# TOP.net
KiCad netlist of a schematic drawn in Altium Designer
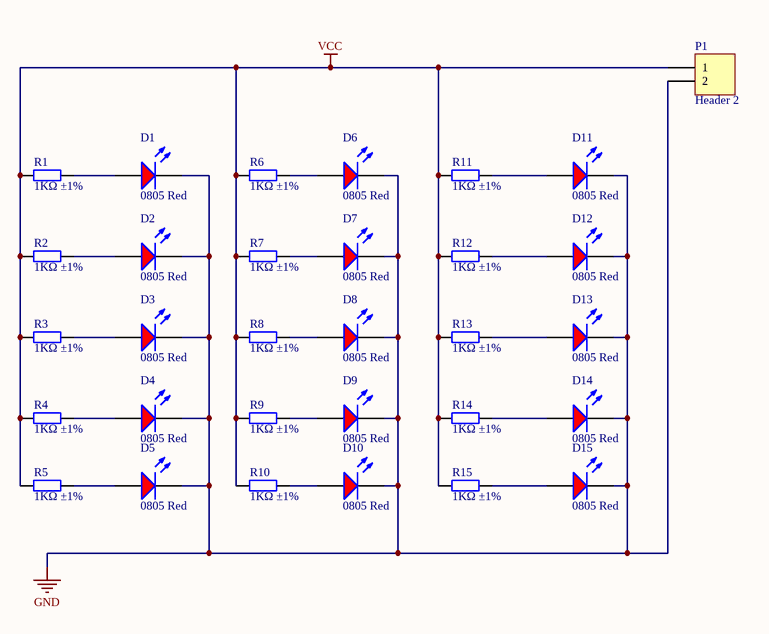
[diagram p0: TOP.SchDoc]

(export (version "E")
  (design (tool "Eeschema 10.0.6"))
  (components
    (comp (ref "D1")
      (value "0805 Red")
      (footprint "0805_LED_S1")
      (description "LED")
      (fields
        (field (name "PARTNUMBER") "FC-2012HRK-620D")
        (field (name "MANUFACTURER") "Foshan NationStar Optoelectronics")
      )
      (libsource (lib "LED") (part "0805 LED Red"))
    )
    (comp (ref "D2")
      (value "0805 Red")
      (footprint "0805_LED_S1")
      (description "LED")
      (fields
        (field (name "PARTNUMBER") "FC-2012HRK-620D")
        (field (name "MANUFACTURER") "Foshan NationStar Optoelectronics")
      )
      (libsource (lib "LED") (part "0805 LED Red"))
    )
    (comp (ref "D3")
      (value "0805 Red")
      (footprint "0805_LED_S1")
      (description "LED")
      (fields
        (field (name "PARTNUMBER") "FC-2012HRK-620D")
        (field (name "MANUFACTURER") "Foshan NationStar Optoelectronics")
      )
      (libsource (lib "LED") (part "0805 LED Red"))
    )
    (comp (ref "D4")
      (value "0805 Red")
      (footprint "0805_LED_S1")
      (description "LED")
      (fields
        (field (name "PARTNUMBER") "FC-2012HRK-620D")
        (field (name "MANUFACTURER") "Foshan NationStar Optoelectronics")
      )
      (libsource (lib "LED") (part "0805 LED Red"))
    )
    (comp (ref "D5")
      (value "0805 Red")
      (footprint "0805_LED_S1")
      (description "LED")
      (fields
        (field (name "PARTNUMBER") "FC-2012HRK-620D")
        (field (name "MANUFACTURER") "Foshan NationStar Optoelectronics")
      )
      (libsource (lib "LED") (part "0805 LED Red"))
    )
    (comp (ref "D6")
      (value "0805 Red")
      (footprint "0805_LED_S1")
      (description "LED")
      (fields
        (field (name "PARTNUMBER") "FC-2012HRK-620D")
        (field (name "MANUFACTURER") "Foshan NationStar Optoelectronics")
      )
      (libsource (lib "LED") (part "0805 LED Red"))
    )
    (comp (ref "D7")
      (value "0805 Red")
      (footprint "0805_LED_S1")
      (description "LED")
      (fields
        (field (name "PARTNUMBER") "FC-2012HRK-620D")
        (field (name "MANUFACTURER") "Foshan NationStar Optoelectronics")
      )
      (libsource (lib "LED") (part "0805 LED Red"))
    )
    (comp (ref "D8")
      (value "0805 Red")
      (footprint "0805_LED_S1")
      (description "LED")
      (fields
        (field (name "PARTNUMBER") "FC-2012HRK-620D")
        (field (name "MANUFACTURER") "Foshan NationStar Optoelectronics")
      )
      (libsource (lib "LED") (part "0805 LED Red"))
    )
    (comp (ref "D9")
      (value "0805 Red")
      (footprint "0805_LED_S1")
      (description "LED")
      (fields
        (field (name "PARTNUMBER") "FC-2012HRK-620D")
        (field (name "MANUFACTURER") "Foshan NationStar Optoelectronics")
      )
      (libsource (lib "LED") (part "0805 LED Red"))
    )
    (comp (ref "D10")
      (value "0805 Red")
      (footprint "0805_LED_S1")
      (description "LED")
      (fields
        (field (name "PARTNUMBER") "FC-2012HRK-620D")
        (field (name "MANUFACTURER") "Foshan NationStar Optoelectronics")
      )
      (libsource (lib "LED") (part "0805 LED Red"))
    )
    (comp (ref "D11")
      (value "0805 Red")
      (footprint "0805_LED_S1")
      (description "LED")
      (fields
        (field (name "PARTNUMBER") "FC-2012HRK-620D")
        (field (name "MANUFACTURER") "Foshan NationStar Optoelectronics")
      )
      (libsource (lib "LED") (part "0805 LED Red"))
    )
    (comp (ref "D12")
      (value "0805 Red")
      (footprint "0805_LED_S1")
      (description "LED")
      (fields
        (field (name "PARTNUMBER") "FC-2012HRK-620D")
        (field (name "MANUFACTURER") "Foshan NationStar Optoelectronics")
      )
      (libsource (lib "LED") (part "0805 LED Red"))
    )
    (comp (ref "D13")
      (value "0805 Red")
      (footprint "0805_LED_S1")
      (description "LED")
      (fields
        (field (name "PARTNUMBER") "FC-2012HRK-620D")
        (field (name "MANUFACTURER") "Foshan NationStar Optoelectronics")
      )
      (libsource (lib "LED") (part "0805 LED Red"))
    )
    (comp (ref "D14")
      (value "0805 Red")
      (footprint "0805_LED_S1")
      (description "LED")
      (fields
        (field (name "PARTNUMBER") "FC-2012HRK-620D")
        (field (name "MANUFACTURER") "Foshan NationStar Optoelectronics")
      )
      (libsource (lib "LED") (part "0805 LED Red"))
    )
    (comp (ref "D15")
      (value "0805 Red")
      (footprint "0805_LED_S1")
      (description "LED")
      (fields
        (field (name "PARTNUMBER") "FC-2012HRK-620D")
        (field (name "MANUFACTURER") "Foshan NationStar Optoelectronics")
      )
      (libsource (lib "LED") (part "0805 LED Red"))
    )
    (comp (ref "P1")
      (value "Header 2")
      (footprint "HDR1X2")
      (description "Header, 2-Pin")
      (fields (field (name "PUBLISHER") "Altium Limited"))
      (libsource (lib "Miscellaneous Connectors") (part "Header 2"))
    )
    (comp (ref "R1")
      (value "1KΩ ±1%")
      (footprint "0805_R")
      (description "Chip resistor")
      (fields (field (name "MANUFACTURER") "Uniroyal Elec") (field (name "PARTNUMBER") "0805W8F1001T5E"))
      (libsource (lib "RES") (part "0805 1K (1001) 1%"))
    )
    (comp (ref "R2")
      (value "1KΩ ±1%")
      (footprint "0805_R")
      (description "Chip resistor")
      (fields (field (name "MANUFACTURER") "Uniroyal Elec") (field (name "PARTNUMBER") "0805W8F1001T5E"))
      (libsource (lib "RES") (part "0805 1K (1001) 1%"))
    )
    (comp (ref "R3")
      (value "1KΩ ±1%")
      (footprint "0805_R")
      (description "Chip resistor")
      (fields (field (name "MANUFACTURER") "Uniroyal Elec") (field (name "PARTNUMBER") "0805W8F1001T5E"))
      (libsource (lib "RES") (part "0805 1K (1001) 1%"))
    )
    (comp (ref "R4")
      (value "1KΩ ±1%")
      (footprint "0805_R")
      (description "Chip resistor")
      (fields (field (name "MANUFACTURER") "Uniroyal Elec") (field (name "PARTNUMBER") "0805W8F1001T5E"))
      (libsource (lib "RES") (part "0805 1K (1001) 1%"))
    )
    (comp (ref "R5")
      (value "1KΩ ±1%")
      (footprint "0805_R")
      (description "Chip resistor")
      (fields (field (name "MANUFACTURER") "Uniroyal Elec") (field (name "PARTNUMBER") "0805W8F1001T5E"))
      (libsource (lib "RES") (part "0805 1K (1001) 1%"))
    )
    (comp (ref "R6")
      (value "1KΩ ±1%")
      (footprint "0805_R")
      (description "Chip resistor")
      (fields (field (name "MANUFACTURER") "Uniroyal Elec") (field (name "PARTNUMBER") "0805W8F1001T5E"))
      (libsource (lib "RES") (part "0805 1K (1001) 1%"))
    )
    (comp (ref "R7")
      (value "1KΩ ±1%")
      (footprint "0805_R")
      (description "Chip resistor")
      (fields (field (name "MANUFACTURER") "Uniroyal Elec") (field (name "PARTNUMBER") "0805W8F1001T5E"))
      (libsource (lib "RES") (part "0805 1K (1001) 1%"))
    )
    (comp (ref "R8")
      (value "1KΩ ±1%")
      (footprint "0805_R")
      (description "Chip resistor")
      (fields (field (name "MANUFACTURER") "Uniroyal Elec") (field (name "PARTNUMBER") "0805W8F1001T5E"))
      (libsource (lib "RES") (part "0805 1K (1001) 1%"))
    )
    (comp (ref "R9")
      (value "1KΩ ±1%")
      (footprint "0805_R")
      (description "Chip resistor")
      (fields (field (name "MANUFACTURER") "Uniroyal Elec") (field (name "PARTNUMBER") "0805W8F1001T5E"))
      (libsource (lib "RES") (part "0805 1K (1001) 1%"))
    )
    (comp (ref "R10")
      (value "1KΩ ±1%")
      (footprint "0805_R")
      (description "Chip resistor")
      (fields (field (name "MANUFACTURER") "Uniroyal Elec") (field (name "PARTNUMBER") "0805W8F1001T5E"))
      (libsource (lib "RES") (part "0805 1K (1001) 1%"))
    )
    (comp (ref "R11")
      (value "1KΩ ±1%")
      (footprint "0805_R")
      (description "Chip resistor")
      (fields (field (name "MANUFACTURER") "Uniroyal Elec") (field (name "PARTNUMBER") "0805W8F1001T5E"))
      (libsource (lib "RES") (part "0805 1K (1001) 1%"))
    )
    (comp (ref "R12")
      (value "1KΩ ±1%")
      (footprint "0805_R")
      (description "Chip resistor")
      (fields (field (name "MANUFACTURER") "Uniroyal Elec") (field (name "PARTNUMBER") "0805W8F1001T5E"))
      (libsource (lib "RES") (part "0805 1K (1001) 1%"))
    )
    (comp (ref "R13")
      (value "1KΩ ±1%")
      (footprint "0805_R")
      (description "Chip resistor")
      (fields (field (name "MANUFACTURER") "Uniroyal Elec") (field (name "PARTNUMBER") "0805W8F1001T5E"))
      (libsource (lib "RES") (part "0805 1K (1001) 1%"))
    )
    (comp (ref "R14")
      (value "1KΩ ±1%")
      (footprint "0805_R")
      (description "Chip resistor")
      (fields (field (name "MANUFACTURER") "Uniroyal Elec") (field (name "PARTNUMBER") "0805W8F1001T5E"))
      (libsource (lib "RES") (part "0805 1K (1001) 1%"))
    )
    (comp (ref "R15")
      (value "1KΩ ±1%")
      (footprint "0805_R")
      (description "Chip resistor")
      (fields (field (name "MANUFACTURER") "Uniroyal Elec") (field (name "PARTNUMBER") "0805W8F1001T5E"))
      (libsource (lib "RES") (part "0805 1K (1001) 1%"))
    )
  )
  (nets
    (net (code "1") (name "GND") (class "Default")
      (node (ref "D1") (pin "K") (pinfunction "K_K") (pintype "passive"))
      (node (ref "D10") (pin "K") (pinfunction "K_K") (pintype "passive"))
      (node (ref "D11") (pin "K") (pinfunction "K_K") (pintype "passive"))
      (node (ref "D12") (pin "K") (pinfunction "K_K") (pintype "passive"))
      (node (ref "D13") (pin "K") (pinfunction "K_K") (pintype "passive"))
      (node (ref "D14") (pin "K") (pinfunction "K_K") (pintype "passive"))
      (node (ref "D15") (pin "K") (pinfunction "K_K") (pintype "passive"))
      (node (ref "D2") (pin "K") (pinfunction "K_K") (pintype "passive"))
      (node (ref "D3") (pin "K") (pinfunction "K_K") (pintype "passive"))
      (node (ref "D4") (pin "K") (pinfunction "K_K") (pintype "passive"))
      (node (ref "D5") (pin "K") (pinfunction "K_K") (pintype "passive"))
      (node (ref "D6") (pin "K") (pinfunction "K_K") (pintype "passive"))
      (node (ref "D7") (pin "K") (pinfunction "K_K") (pintype "passive"))
      (node (ref "D8") (pin "K") (pinfunction "K_K") (pintype "passive"))
      (node (ref "D9") (pin "K") (pinfunction "K_K") (pintype "passive"))
      (node (ref "P1") (pin "2") (pinfunction "2_2") (pintype "passive"))
    )
    (net (code "2") (name "Net-(D1-PadA)") (class "Default")
      (node (ref "D1") (pin "A") (pinfunction "A_A") (pintype "passive"))
      (node (ref "R1") (pin "2") (pinfunction "2_2") (pintype "passive"))
    )
    (net (code "3") (name "Net-(D2-PadA)") (class "Default")
      (node (ref "D2") (pin "A") (pinfunction "A_A") (pintype "passive"))
      (node (ref "R2") (pin "2") (pinfunction "2_2") (pintype "passive"))
    )
    (net (code "4") (name "Net-(D3-PadA)") (class "Default")
      (node (ref "D3") (pin "A") (pinfunction "A_A") (pintype "passive"))
      (node (ref "R3") (pin "2") (pinfunction "2_2") (pintype "passive"))
    )
    (net (code "5") (name "Net-(D4-PadA)") (class "Default")
      (node (ref "D4") (pin "A") (pinfunction "A_A") (pintype "passive"))
      (node (ref "R4") (pin "2") (pinfunction "2_2") (pintype "passive"))
    )
    (net (code "6") (name "Net-(D5-PadA)") (class "Default")
      (node (ref "D5") (pin "A") (pinfunction "A_A") (pintype "passive"))
      (node (ref "R5") (pin "2") (pinfunction "2_2") (pintype "passive"))
    )
    (net (code "7") (name "Net-(D6-PadA)") (class "Default")
      (node (ref "D6") (pin "A") (pinfunction "A_A") (pintype "passive"))
      (node (ref "R6") (pin "2") (pinfunction "2_2") (pintype "passive"))
    )
    (net (code "8") (name "Net-(D7-PadA)") (class "Default")
      (node (ref "D7") (pin "A") (pinfunction "A_A") (pintype "passive"))
      (node (ref "R7") (pin "2") (pinfunction "2_2") (pintype "passive"))
    )
    (net (code "9") (name "Net-(D8-PadA)") (class "Default")
      (node (ref "D8") (pin "A") (pinfunction "A_A") (pintype "passive"))
      (node (ref "R8") (pin "2") (pinfunction "2_2") (pintype "passive"))
    )
    (net (code "10") (name "Net-(D9-PadA)") (class "Default")
      (node (ref "D9") (pin "A") (pinfunction "A_A") (pintype "passive"))
      (node (ref "R9") (pin "2") (pinfunction "2_2") (pintype "passive"))
    )
    (net (code "11") (name "Net-(D10-PadA)") (class "Default")
      (node (ref "D10") (pin "A") (pinfunction "A_A") (pintype "passive"))
      (node (ref "R10") (pin "2") (pinfunction "2_2") (pintype "passive"))
    )
    (net (code "12") (name "Net-(D11-PadA)") (class "Default")
      (node (ref "D11") (pin "A") (pinfunction "A_A") (pintype "passive"))
      (node (ref "R11") (pin "2") (pinfunction "2_2") (pintype "passive"))
    )
    (net (code "13") (name "Net-(D12-PadA)") (class "Default")
      (node (ref "D12") (pin "A") (pinfunction "A_A") (pintype "passive"))
      (node (ref "R12") (pin "2") (pinfunction "2_2") (pintype "passive"))
    )
    (net (code "14") (name "Net-(D13-PadA)") (class "Default")
      (node (ref "D13") (pin "A") (pinfunction "A_A") (pintype "passive"))
      (node (ref "R13") (pin "2") (pinfunction "2_2") (pintype "passive"))
    )
    (net (code "15") (name "Net-(D14-PadA)") (class "Default")
      (node (ref "D14") (pin "A") (pinfunction "A_A") (pintype "passive"))
      (node (ref "R14") (pin "2") (pinfunction "2_2") (pintype "passive"))
    )
    (net (code "16") (name "Net-(D15-PadA)") (class "Default")
      (node (ref "D15") (pin "A") (pinfunction "A_A") (pintype "passive"))
      (node (ref "R15") (pin "2") (pinfunction "2_2") (pintype "passive"))
    )
    (net (code "17") (name "VCC") (class "Default")
      (node (ref "P1") (pin "1") (pinfunction "1_1") (pintype "passive"))
      (node (ref "R1") (pin "1") (pinfunction "1_1") (pintype "passive"))
      (node (ref "R10") (pin "1") (pinfunction "1_1") (pintype "passive"))
      (node (ref "R11") (pin "1") (pinfunction "1_1") (pintype "passive"))
      (node (ref "R12") (pin "1") (pinfunction "1_1") (pintype "passive"))
      (node (ref "R13") (pin "1") (pinfunction "1_1") (pintype "passive"))
      (node (ref "R14") (pin "1") (pinfunction "1_1") (pintype "passive"))
      (node (ref "R15") (pin "1") (pinfunction "1_1") (pintype "passive"))
      (node (ref "R2") (pin "1") (pinfunction "1_1") (pintype "passive"))
      (node (ref "R3") (pin "1") (pinfunction "1_1") (pintype "passive"))
      (node (ref "R4") (pin "1") (pinfunction "1_1") (pintype "passive"))
      (node (ref "R5") (pin "1") (pinfunction "1_1") (pintype "passive"))
      (node (ref "R6") (pin "1") (pinfunction "1_1") (pintype "passive"))
      (node (ref "R7") (pin "1") (pinfunction "1_1") (pintype "passive"))
      (node (ref "R8") (pin "1") (pinfunction "1_1") (pintype "passive"))
      (node (ref "R9") (pin "1") (pinfunction "1_1") (pintype "passive"))
    )
  )
)
